# Transceiver_2.net
KiCad netlist of a schematic drawn in EAGLE
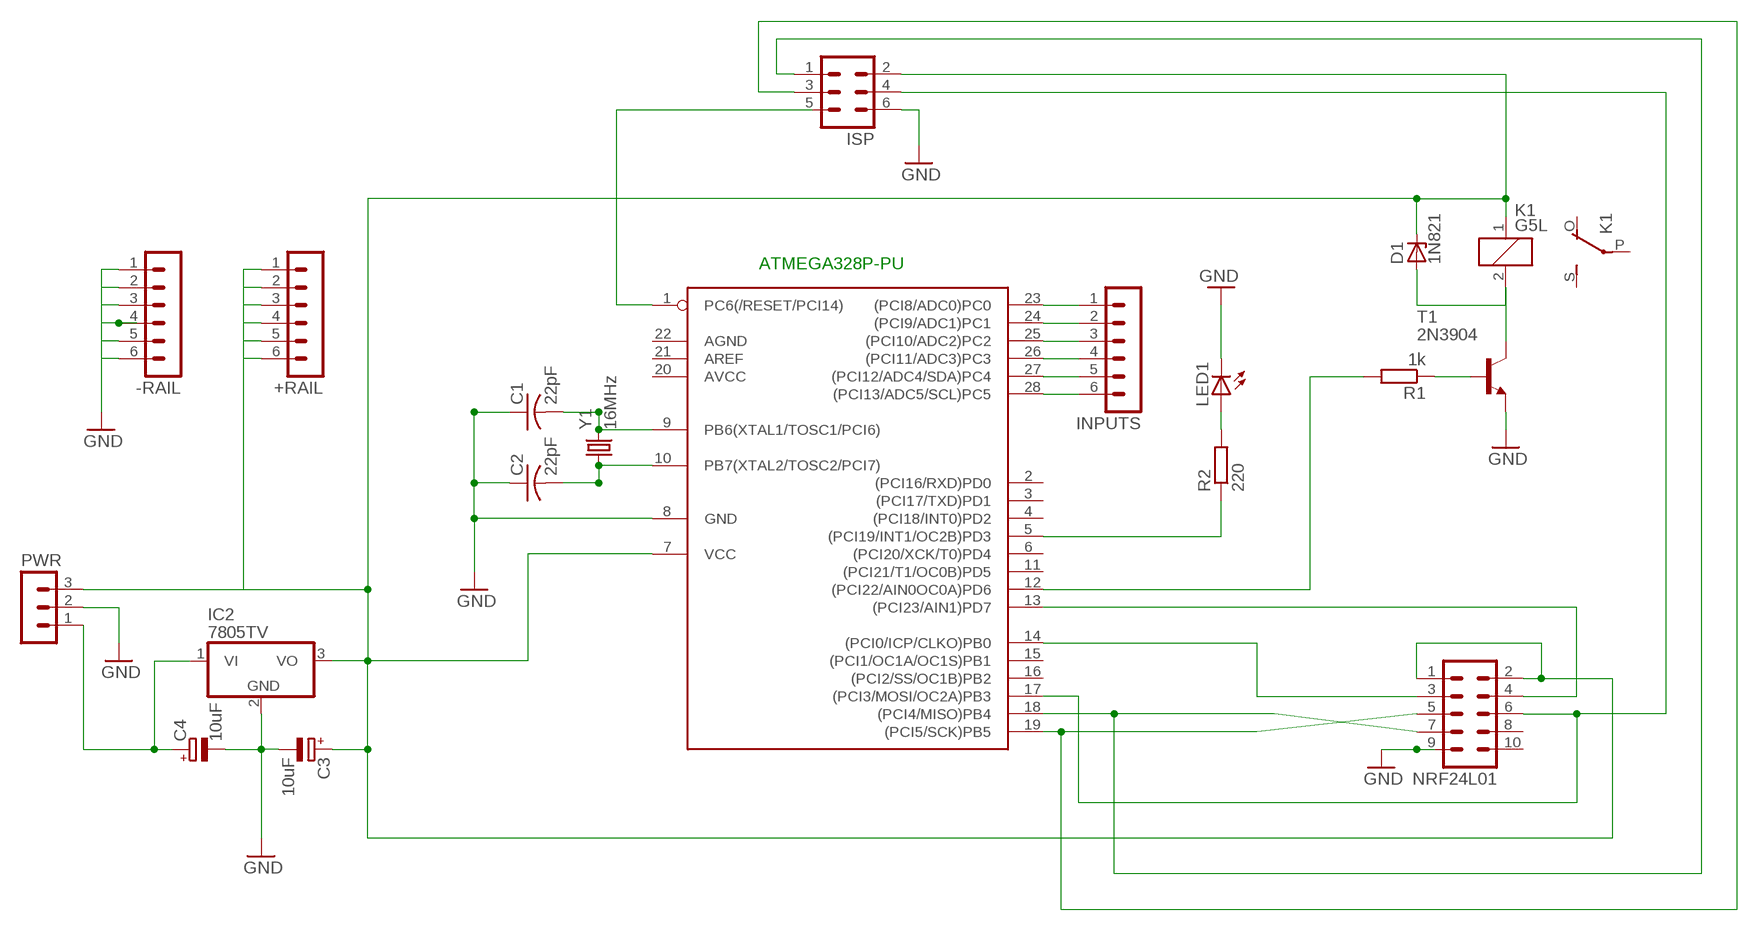
[diagram p0: schematic, sheet 1]

(export (version "E")
  (design (tool "Eeschema 10.0.6"))
  (components
    (comp (ref "+RAIL")
      (value "MA06-1")
      (footprint "eagle-import:MA06-1")
      (fields (field (name "OC_FARNELL") "unknown") (field (name "OC_NEWARK") "unknown"))
      (libsource (lib "eagle-import") (part "MA06-1"))
    )
    (comp (ref "-RAIL")
      (value "MA06-1")
      (footprint "eagle-import:MA06-1")
      (fields (field (name "OC_FARNELL") "unknown") (field (name "OC_NEWARK") "unknown"))
      (libsource (lib "eagle-import") (part "MA06-1"))
    )
    (comp (ref "C1")
      (value "22pF")
      (footprint "eagle-import:C025-024X044")
      (libsource (lib "eagle-import") (part "C-US025-024X044"))
    )
    (comp (ref "C2")
      (value "22pF")
      (footprint "eagle-import:C025-024X044")
      (libsource (lib "eagle-import") (part "C-US025-024X044"))
    )
    (comp (ref "C3")
      (value "10uF")
      (footprint "eagle-import:E2-5")
      (libsource (lib "eagle-import") (part "CPOL-EUE2-5"))
    )
    (comp (ref "C4")
      (value "10uF")
      (footprint "eagle-import:E2-5")
      (libsource (lib "eagle-import") (part "CPOL-EUE2-5"))
    )
    (comp (ref "D1")
      (value "1N821")
      (footprint "eagle-import:DO35Z10")
      (libsource (lib "eagle-import") (part "1N821"))
    )
    (comp (ref "IC1")
      (value "ATMEGA168-20P")
      (footprint "eagle-import:DIL28-3")
      (libsource (lib "eagle-import") (part "ATMEGA168P-20"))
    )
    (comp (ref "IC2")
      (value "7805TV")
      (footprint "eagle-import:TO220V")
      (libsource (lib "eagle-import") (part "78TV05"))
    )
    (comp (ref "INPUTS")
      (value "MA06-1")
      (footprint "eagle-import:MA06-1")
      (libsource (lib "eagle-import") (part "MA06-1"))
    )
    (comp (ref "ISP")
      (value "MA03-2")
      (footprint "eagle-import:MA03-2")
      (libsource (lib "eagle-import") (part "MA03-2"))
    )
    (comp (ref "K1")
      (value "G5L")
      (footprint "eagle-import:G5LE")
      (libsource (lib "eagle-import") (part "G5L"))
    )
    (comp (ref "LED1")
      (value "LED3MM")
      (footprint "eagle-import:LED3MM")
      (libsource (lib "eagle-import") (part "LED3MM"))
    )
    (comp (ref "NRF24L01")
      (value "MA05-2")
      (footprint "eagle-import:MA05-2")
      (libsource (lib "eagle-import") (part "MA05-2"))
    )
    (comp (ref "PWR")
      (value "MA03-1")
      (footprint "eagle-import:MA03-1")
      (fields (field (name "OC_FARNELL") "unknown") (field (name "OC_NEWARK") "unknown"))
      (libsource (lib "eagle-import") (part "MA03-1"))
    )
    (comp (ref "R1")
      (value "1k")
      (footprint "eagle-import:0204_7")
      (libsource (lib "eagle-import") (part "R-EU_0204/7"))
    )
    (comp (ref "R2")
      (value "220")
      (footprint "eagle-import:0204_7")
      (libsource (lib "eagle-import") (part "R-EU_0204/7"))
    )
    (comp (ref "T1")
      (value "2N3904")
      (footprint "eagle-import:TO92")
      (libsource (lib "eagle-import") (part "2N3904"))
    )
    (comp (ref "Y1")
      (value "16MHz")
      (footprint "eagle-import:HC49US")
      (libsource (lib "eagle-import") (part "CRYSTALHC49US"))
    )
  )
  (nets
    (net (code "1") (name "GND") (class "Default")
      (node (ref "-RAIL") (pin "1") (pinfunction "1_1") (pintype "passive"))
      (node (ref "-RAIL") (pin "2") (pinfunction "2_2") (pintype "passive"))
      (node (ref "-RAIL") (pin "3") (pinfunction "3_3") (pintype "passive"))
      (node (ref "-RAIL") (pin "4") (pinfunction "4_4") (pintype "passive"))
      (node (ref "-RAIL") (pin "5") (pinfunction "5_5") (pintype "passive"))
      (node (ref "-RAIL") (pin "6") (pinfunction "6_6") (pintype "passive"))
      (node (ref "C1") (pin "1") (pinfunction "1_1") (pintype "passive"))
      (node (ref "C2") (pin "1") (pinfunction "1_1") (pintype "passive"))
      (node (ref "C3") (pin "-") (pinfunction "-_-") (pintype "passive"))
      (node (ref "C4") (pin "-") (pinfunction "-_-") (pintype "passive"))
      (node (ref "IC1") (pin "8") (pinfunction "GND_8") (pintype "bidirectional"))
      (node (ref "IC2") (pin "2") (pinfunction "GND_2") (pintype "passive"))
      (node (ref "ISP") (pin "6") (pinfunction "6_6") (pintype "passive"))
      (node (ref "LED1") (pin "K") (pinfunction "C_K") (pintype "passive"))
      (node (ref "NRF24L01") (pin "9") (pinfunction "9_9") (pintype "passive"))
      (node (ref "PWR") (pin "2") (pinfunction "2_2") (pintype "passive"))
      (node (ref "T1") (pin "3") (pinfunction "E_3") (pintype "passive"))
    )
    (net (code "2") (name "Net-(IC1-(PCI0{slash}ICP{slash}CLKO)PB0)") (class "Default")
      (node (ref "IC1") (pin "14") (pinfunction "(PCI0/ICP/CLKO)PB0_14") (pintype "bidirectional"))
      (node (ref "NRF24L01") (pin "3") (pinfunction "3_3") (pintype "passive"))
    )
    (net (code "3") (name "Net-(IC1-(PCI3{slash}MOSI{slash}OC2A)PB3)") (class "Default")
      (node (ref "IC1") (pin "17") (pinfunction "(PCI3/MOSI/OC2A)PB3_17") (pintype "bidirectional"))
      (node (ref "ISP") (pin "4") (pinfunction "4_4") (pintype "passive"))
      (node (ref "NRF24L01") (pin "6") (pinfunction "6_6") (pintype "passive"))
    )
    (net (code "4") (name "Net-(IC1-(PCI4{slash}MISO)PB4)") (class "Default")
      (node (ref "IC1") (pin "18") (pinfunction "(PCI4/MISO)PB4_18") (pintype "bidirectional"))
      (node (ref "ISP") (pin "1") (pinfunction "1_1") (pintype "passive"))
      (node (ref "NRF24L01") (pin "7") (pinfunction "7_7") (pintype "passive"))
    )
    (net (code "5") (name "Net-(IC1-(PCI5{slash}SCK)PB5)") (class "Default")
      (node (ref "IC1") (pin "19") (pinfunction "(PCI5/SCK)PB5_19") (pintype "bidirectional"))
      (node (ref "ISP") (pin "3") (pinfunction "3_3") (pintype "passive"))
      (node (ref "NRF24L01") (pin "5") (pinfunction "5_5") (pintype "passive"))
    )
    (net (code "6") (name "Net-(IC1-(PCI8{slash}ADC0)PC0)") (class "Default")
      (node (ref "IC1") (pin "23") (pinfunction "(PCI8/ADC0)PC0_23") (pintype "bidirectional"))
      (node (ref "INPUTS") (pin "1") (pinfunction "1_1") (pintype "passive"))
    )
    (net (code "7") (name "Net-(IC1-(PCI9{slash}ADC1)PC1)") (class "Default")
      (node (ref "IC1") (pin "24") (pinfunction "(PCI9/ADC1)PC1_24") (pintype "bidirectional"))
      (node (ref "INPUTS") (pin "2") (pinfunction "2_2") (pintype "passive"))
    )
    (net (code "8") (name "Net-(IC1-(PCI10{slash}ADC2)PC2)") (class "Default")
      (node (ref "IC1") (pin "25") (pinfunction "(PCI10/ADC2)PC2_25") (pintype "bidirectional"))
      (node (ref "INPUTS") (pin "3") (pinfunction "3_3") (pintype "passive"))
    )
    (net (code "9") (name "Net-(IC1-(PCI11{slash}ADC3)PC3)") (class "Default")
      (node (ref "IC1") (pin "26") (pinfunction "(PCI11/ADC3)PC3_26") (pintype "bidirectional"))
      (node (ref "INPUTS") (pin "4") (pinfunction "4_4") (pintype "passive"))
    )
    (net (code "10") (name "Net-(IC1-(PCI12{slash}ADC4{slash}SDA)PC4)") (class "Default")
      (node (ref "IC1") (pin "27") (pinfunction "(PCI12/ADC4/SDA)PC4_27") (pintype "bidirectional"))
      (node (ref "INPUTS") (pin "5") (pinfunction "5_5") (pintype "passive"))
    )
    (net (code "11") (name "Net-(IC1-(PCI13{slash}ADC5{slash}SCL)PC5)") (class "Default")
      (node (ref "IC1") (pin "28") (pinfunction "(PCI13/ADC5/SCL)PC5_28") (pintype "bidirectional"))
      (node (ref "INPUTS") (pin "6") (pinfunction "6_6") (pintype "passive"))
    )
    (net (code "12") (name "Net-(IC1-(PCI19{slash}INT1{slash}OC2B)PD3)") (class "Default")
      (node (ref "IC1") (pin "5") (pinfunction "(PCI19/INT1/OC2B)PD3_5") (pintype "bidirectional"))
      (node (ref "R2") (pin "1") (pinfunction "1_1") (pintype "passive"))
    )
    (net (code "13") (name "Net-(IC1-(PCI22{slash}AIN0OC0A)PD6)") (class "Default")
      (node (ref "IC1") (pin "12") (pinfunction "(PCI22/AIN0OC0A)PD6_12") (pintype "bidirectional"))
      (node (ref "R1") (pin "2") (pinfunction "2_2") (pintype "passive"))
    )
    (net (code "14") (name "Net-(IC1-(PCI23{slash}AIN1)PD7)") (class "Default")
      (node (ref "IC1") (pin "13") (pinfunction "(PCI23/AIN1)PD7_13") (pintype "bidirectional"))
      (node (ref "NRF24L01") (pin "4") (pinfunction "4_4") (pintype "passive"))
    )
    (net (code "15") (name "Net-(IC1-PB6(XTAL1{slash}TOSC1{slash}PCI6))") (class "Default")
      (node (ref "C1") (pin "2") (pinfunction "2_2") (pintype "passive"))
      (node (ref "IC1") (pin "9") (pinfunction "PB6(XTAL1/TOSC1/PCI6)_9") (pintype "bidirectional"))
      (node (ref "Y1") (pin "2") (pinfunction "2_2") (pintype "passive"))
    )
    (net (code "16") (name "Net-(IC1-PB7(XTAL2{slash}TOSC2{slash}PCI7))") (class "Default")
      (node (ref "C2") (pin "2") (pinfunction "2_2") (pintype "passive"))
      (node (ref "IC1") (pin "10") (pinfunction "PB7(XTAL2/TOSC2/PCI7)_10") (pintype "bidirectional"))
      (node (ref "Y1") (pin "1") (pinfunction "1_1") (pintype "passive"))
    )
    (net (code "17") (name "Net-(IC1-PC6({slash}RESET{slash}PCI14))") (class "Default")
      (node (ref "IC1") (pin "1") (pinfunction "PC6(/RESET/PCI14)_1") (pintype "bidirectional"))
      (node (ref "ISP") (pin "5") (pinfunction "5_5") (pintype "passive"))
    )
    (net (code "18") (name "Net-(IC1-VCC)") (class "Default")
      (node (ref "+RAIL") (pin "1") (pinfunction "1_1") (pintype "passive"))
      (node (ref "+RAIL") (pin "2") (pinfunction "2_2") (pintype "passive"))
      (node (ref "+RAIL") (pin "3") (pinfunction "3_3") (pintype "passive"))
      (node (ref "+RAIL") (pin "4") (pinfunction "4_4") (pintype "passive"))
      (node (ref "+RAIL") (pin "5") (pinfunction "5_5") (pintype "passive"))
      (node (ref "+RAIL") (pin "6") (pinfunction "6_6") (pintype "passive"))
      (node (ref "C3") (pin "+") (pinfunction "+_+") (pintype "passive"))
      (node (ref "D1") (pin "C") (pinfunction "C_C") (pintype "passive"))
      (node (ref "IC1") (pin "7") (pinfunction "VCC_7") (pintype "bidirectional"))
      (node (ref "IC2") (pin "3") (pinfunction "VO_3") (pintype "passive"))
      (node (ref "ISP") (pin "2") (pinfunction "2_2") (pintype "passive"))
      (node (ref "K1") (pin "1") (pinfunction "1_1") (pintype "passive"))
      (node (ref "NRF24L01") (pin "1") (pinfunction "1_1") (pintype "passive"))
      (node (ref "NRF24L01") (pin "2") (pinfunction "2_2") (pintype "passive"))
      (node (ref "PWR") (pin "3") (pinfunction "3_3") (pintype "passive"))
    )
    (net (code "19") (name "Net-(IC2-VI)") (class "Default")
      (node (ref "C4") (pin "+") (pinfunction "+_+") (pintype "passive"))
      (node (ref "IC2") (pin "1") (pinfunction "VI_1") (pintype "input"))
      (node (ref "PWR") (pin "1") (pinfunction "1_1") (pintype "passive"))
    )
    (net (code "20") (name "Net-(LED1-PadA)") (class "Default")
      (node (ref "LED1") (pin "A") (pinfunction "A_A") (pintype "passive"))
      (node (ref "R2") (pin "2") (pinfunction "2_2") (pintype "passive"))
    )
    (net (code "21") (name "Net-(T1-B)") (class "Default")
      (node (ref "R1") (pin "1") (pinfunction "1_1") (pintype "passive"))
      (node (ref "T1") (pin "2") (pinfunction "B_2") (pintype "passive"))
    )
    (net (code "22") (name "Net-(T1-C)") (class "Default")
      (node (ref "D1") (pin "A") (pinfunction "A_A") (pintype "passive"))
      (node (ref "K1") (pin "2") (pinfunction "2_2") (pintype "passive"))
      (node (ref "T1") (pin "1") (pinfunction "C_1") (pintype "passive"))
    )
    (net (code "23") (name "unconnected-(IC1-(PCI1{slash}OC1A{slash}OC1S)PB1-Pad15)") (class "Default")
      (node (ref "IC1") (pin "15") (pinfunction "(PCI1/OC1A/OC1S)PB1_15") (pintype "bidirectional"))
    )
    (net (code "24") (name "unconnected-(IC1-(PCI2{slash}SS{slash}OC1B)PB2-Pad16)") (class "Default")
      (node (ref "IC1") (pin "16") (pinfunction "(PCI2/SS/OC1B)PB2_16") (pintype "bidirectional"))
    )
    (net (code "25") (name "unconnected-(IC1-(PCI16{slash}RXD)PD0-Pad2)") (class "Default")
      (node (ref "IC1") (pin "2") (pinfunction "(PCI16/RXD)PD0_2") (pintype "bidirectional"))
    )
    (net (code "26") (name "unconnected-(IC1-(PCI17{slash}TXD)PD1-Pad3)") (class "Default")
      (node (ref "IC1") (pin "3") (pinfunction "(PCI17/TXD)PD1_3") (pintype "bidirectional"))
    )
    (net (code "27") (name "unconnected-(IC1-(PCI18{slash}INT0)PD2-Pad4)") (class "Default")
      (node (ref "IC1") (pin "4") (pinfunction "(PCI18/INT0)PD2_4") (pintype "bidirectional"))
    )
    (net (code "28") (name "unconnected-(IC1-(PCI20{slash}XCK{slash}T0)PD4-Pad6)") (class "Default")
      (node (ref "IC1") (pin "6") (pinfunction "(PCI20/XCK/T0)PD4_6") (pintype "bidirectional"))
    )
    (net (code "29") (name "unconnected-(IC1-(PCI21{slash}T1{slash}OC0B)PD5-Pad11)") (class "Default")
      (node (ref "IC1") (pin "11") (pinfunction "(PCI21/T1/OC0B)PD5_11") (pintype "bidirectional"))
    )
    (net (code "30") (name "unconnected-(IC1-AGND-Pad22)") (class "Default")
      (node (ref "IC1") (pin "22") (pinfunction "AGND_22") (pintype "bidirectional"))
    )
    (net (code "31") (name "unconnected-(IC1-AREF-Pad21)") (class "Default")
      (node (ref "IC1") (pin "21") (pinfunction "AREF_21") (pintype "bidirectional"))
    )
    (net (code "32") (name "unconnected-(IC1-AVCC-Pad20)") (class "Default")
      (node (ref "IC1") (pin "20") (pinfunction "AVCC_20") (pintype "bidirectional"))
    )
    (net (code "33") (name "unconnected-(K1-PadO)") (class "Default")
      (node (ref "K1") (pin "O") (pinfunction "O_O") (pintype "passive"))
    )
    (net (code "34") (name "unconnected-(K1-PadP)") (class "Default")
      (node (ref "K1") (pin "P") (pinfunction "P_P") (pintype "passive"))
    )
    (net (code "35") (name "unconnected-(K1-PadS)") (class "Default")
      (node (ref "K1") (pin "S") (pinfunction "S_S") (pintype "passive"))
    )
    (net (code "36") (name "unconnected-(NRF24L01-Pad8)") (class "Default")
      (node (ref "NRF24L01") (pin "8") (pinfunction "8_8") (pintype "passive"))
    )
    (net (code "37") (name "unconnected-(NRF24L01-Pad10)") (class "Default")
      (node (ref "NRF24L01") (pin "10") (pinfunction "10_10") (pintype "passive"))
    )
  )
)
